# spindle_controller.net
KiCad netlist of a schematic drawn in EAGLE
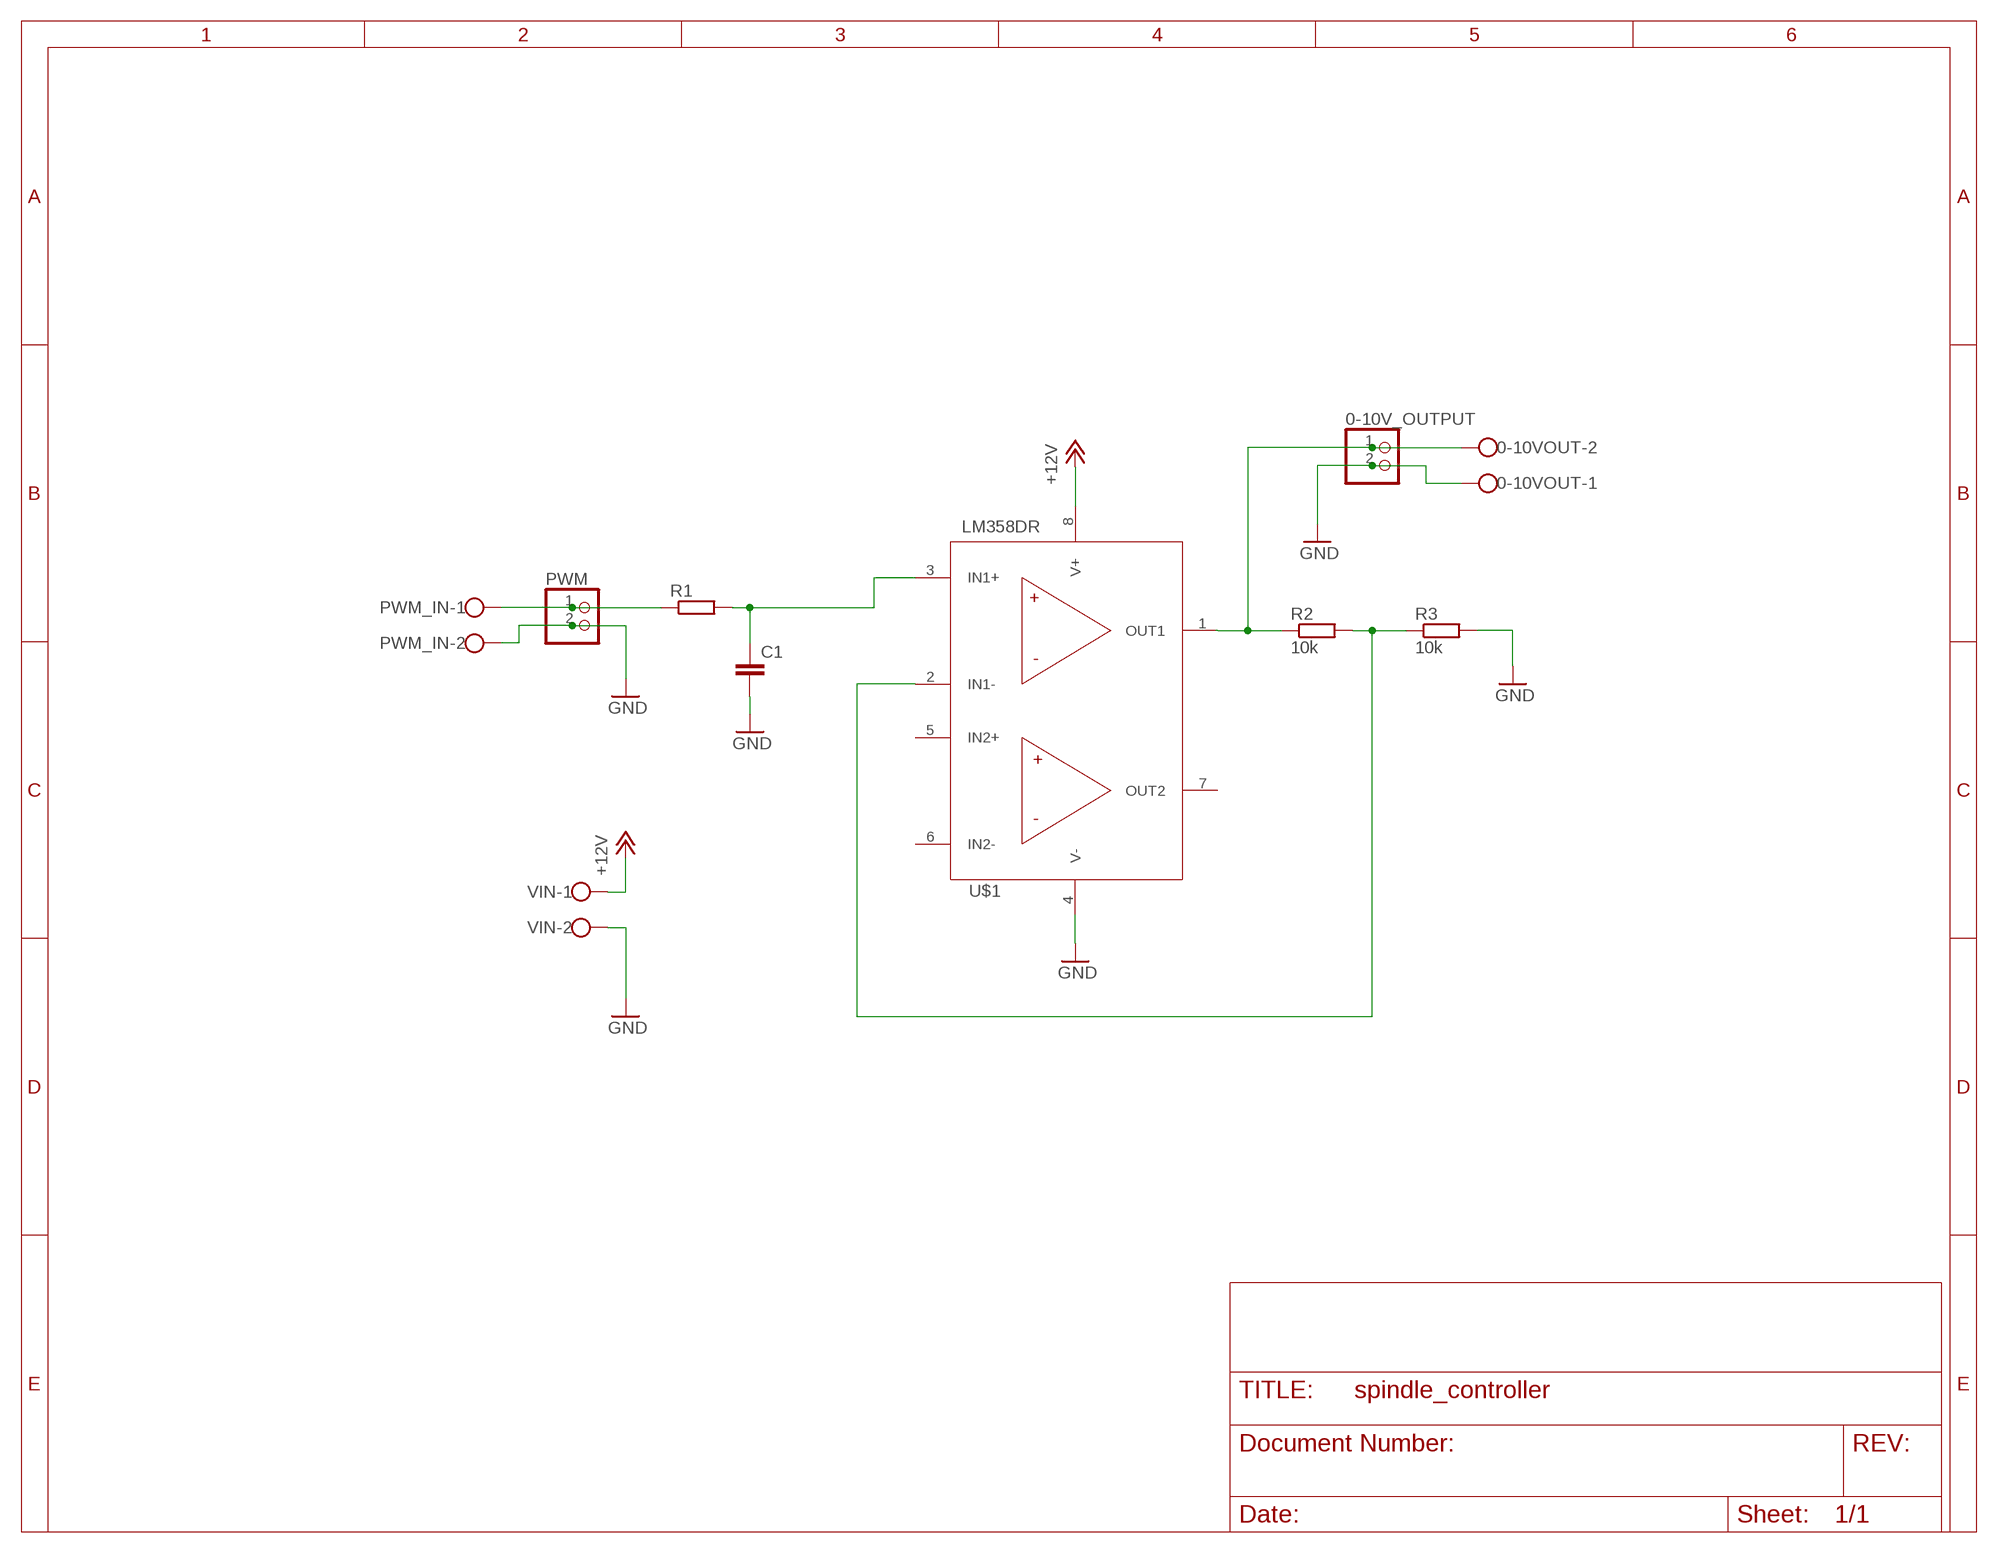
[diagram p0: schematic, sheet 1]

(export (version "E")
  (design (tool "Eeschema 10.0.6"))
  (components
    (comp (ref "0-10VOUT")
      (value "W237-102")
      (footprint "eagle-import:W237-102")
      (fields (field (name "MPN") "237-102"))
      (libsource (lib "eagle-import") (part "W237-102"))
    )
    (comp (ref "0-10V_OUTPUT")
      (value "PINHD-1X2")
      (footprint "eagle-import:1X02")
      (libsource (lib "eagle-import") (part "PINHD-1X2"))
    )
    (comp (ref "C1")
      (value "C-EUC0603")
      (footprint "eagle-import:C0603")
      (libsource (lib "eagle-import") (part "C-EUC0603"))
    )
    (comp (ref "PWM")
      (value "PINHD-1X2")
      (footprint "eagle-import:1X02")
      (libsource (lib "eagle-import") (part "PINHD-1X2"))
    )
    (comp (ref "PWM_IN")
      (value "W237-102")
      (footprint "eagle-import:W237-102")
      (fields (field (name "MPN") "237-102"))
      (libsource (lib "eagle-import") (part "W237-102"))
    )
    (comp (ref "R1")
      (value "R-EU_R0603")
      (footprint "eagle-import:R0603")
      (libsource (lib "eagle-import") (part "R-EU_R0603"))
    )
    (comp (ref "R2")
      (value "10k")
      (footprint "eagle-import:R0603")
      (libsource (lib "eagle-import") (part "R-EU_R0603"))
    )
    (comp (ref "R3")
      (value "10k")
      (footprint "eagle-import:R0603")
      (libsource (lib "eagle-import") (part "R-EU_R0603"))
    )
    (comp (ref "U$1")
      (value "LM358DRLM358DR_SOIC8")
      (footprint "eagle-import:SOIC127P599X175-8N")
      (libsource (lib "eagle-import") (part "LM358DRLM358DR_SOIC8"))
    )
    (comp (ref "VIN")
      (value "W237-102")
      (footprint "eagle-import:W237-102")
      (fields (field (name "MPN") "237-102"))
      (libsource (lib "eagle-import") (part "W237-102"))
    )
  )
  (nets
    (net (code "1") (name "+12V") (class "Default")
      (node (ref "U$1") (pin "8") (pinfunction "V+_8") (pintype "bidirectional"))
      (node (ref "VIN") (pin "1") (pinfunction "KL_1") (pintype "passive"))
    )
    (net (code "2") (name "GND") (class "Default")
      (node (ref "0-10VOUT") (pin "1") (pinfunction "KL_1") (pintype "passive"))
      (node (ref "0-10V_OUTPUT") (pin "2") (pinfunction "2_2") (pintype "passive"))
      (node (ref "C1") (pin "2") (pinfunction "2_2") (pintype "passive"))
      (node (ref "PWM") (pin "2") (pinfunction "2_2") (pintype "passive"))
      (node (ref "PWM_IN") (pin "2") (pinfunction "KL_2") (pintype "passive"))
      (node (ref "R3") (pin "2") (pinfunction "2_2") (pintype "passive"))
      (node (ref "U$1") (pin "4") (pinfunction "V-_4") (pintype "bidirectional"))
      (node (ref "VIN") (pin "2") (pinfunction "KL_2") (pintype "passive"))
    )
    (net (code "3") (name "Net-(0-10VOUTB-KL)") (class "Default")
      (node (ref "0-10VOUT") (pin "2") (pinfunction "KL_2") (pintype "passive"))
      (node (ref "0-10V_OUTPUT") (pin "1") (pinfunction "1_1") (pintype "passive"))
      (node (ref "R2") (pin "1") (pinfunction "1_1") (pintype "passive"))
      (node (ref "U$1") (pin "1") (pinfunction "OUT1_1") (pintype "bidirectional"))
    )
    (net (code "4") (name "Net-(PWM_INA-KL)") (class "Default")
      (node (ref "PWM") (pin "1") (pinfunction "1_1") (pintype "passive"))
      (node (ref "PWM_IN") (pin "1") (pinfunction "KL_1") (pintype "passive"))
      (node (ref "R1") (pin "1") (pinfunction "1_1") (pintype "passive"))
    )
    (net (code "5") (name "Net-(U$1-IN1+)") (class "Default")
      (node (ref "C1") (pin "1") (pinfunction "1_1") (pintype "passive"))
      (node (ref "R1") (pin "2") (pinfunction "2_2") (pintype "passive"))
      (node (ref "U$1") (pin "3") (pinfunction "IN1+_3") (pintype "bidirectional"))
    )
    (net (code "6") (name "Net-(U$1-IN1-)") (class "Default")
      (node (ref "R2") (pin "2") (pinfunction "2_2") (pintype "passive"))
      (node (ref "R3") (pin "1") (pinfunction "1_1") (pintype "passive"))
      (node (ref "U$1") (pin "2") (pinfunction "IN1-_2") (pintype "bidirectional"))
    )
    (net (code "7") (name "unconnected-(U$1-IN2+-Pad5)") (class "Default")
      (node (ref "U$1") (pin "5") (pinfunction "IN2+_5") (pintype "bidirectional"))
    )
    (net (code "8") (name "unconnected-(U$1-IN2--Pad6)") (class "Default")
      (node (ref "U$1") (pin "6") (pinfunction "IN2-_6") (pintype "bidirectional"))
    )
    (net (code "9") (name "unconnected-(U$1-OUT2-Pad7)") (class "Default")
      (node (ref "U$1") (pin "7") (pinfunction "OUT2_7") (pintype "bidirectional"))
    )
  )
)
